# RLS.net
KiCad netlist of a schematic drawn in Altium Designer
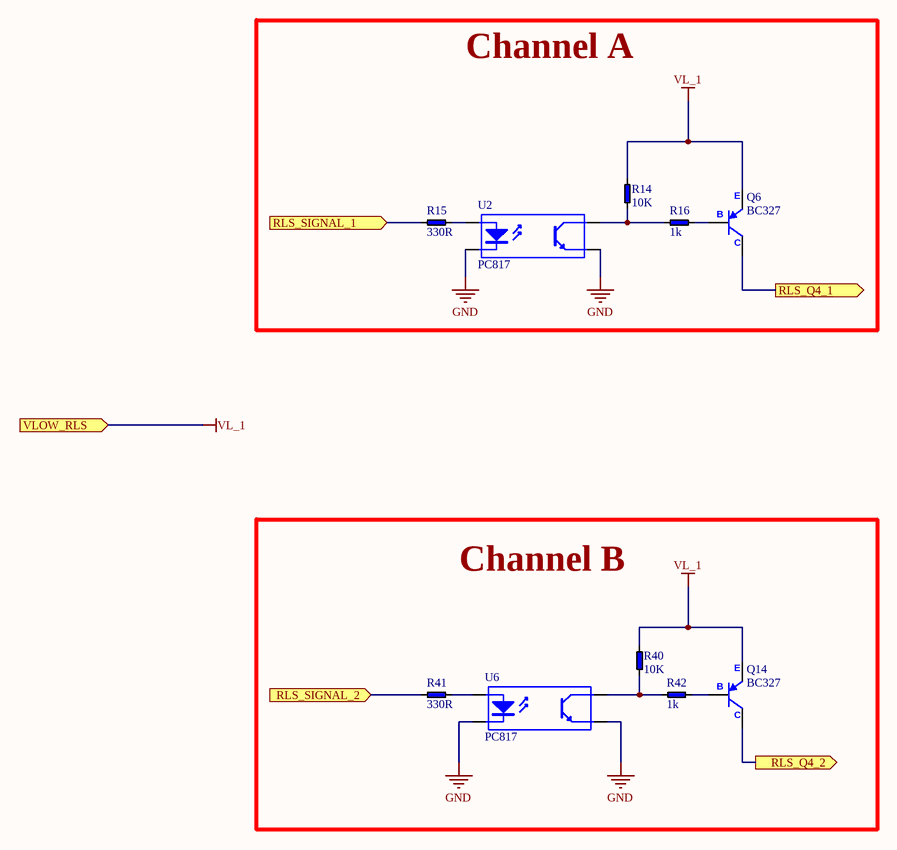
[diagram p0: RLS.SchDoc]

(export (version "E")
  (design (tool "Eeschema 10.0.6"))
  (components
    (comp (ref "Q6")
      (value "BC327")
      (footprint "Transistor - duplicate3")
      (libsource (lib "Altium_Abbas") (part "PNP"))
    )
    (comp (ref "Q14")
      (value "BC327")
      (footprint "Transistor - duplicate3")
      (libsource (lib "Altium_Abbas") (part "PNP"))
    )
    (comp (ref "R14")
      (value "10K")
      (footprint "RESISTOR _9")
      (libsource (lib "Altium_Abbas") (part "RESISTOR"))
    )
    (comp (ref "R15")
      (value "330R")
      (footprint "RESISTOR _9")
      (libsource (lib "Altium_Abbas") (part "RESISTOR"))
    )
    (comp (ref "R16")
      (value "1k")
      (footprint "RESISTOR _9")
      (libsource (lib "Altium_Abbas") (part "RESISTOR"))
    )
    (comp (ref "R40")
      (value "10K")
      (footprint "RESISTOR _9")
      (libsource (lib "Altium_Abbas") (part "RESISTOR"))
    )
    (comp (ref "R41")
      (value "330R")
      (footprint "RESISTOR _9")
      (libsource (lib "Altium_Abbas") (part "RESISTOR"))
    )
    (comp (ref "R42")
      (value "1k")
      (footprint "RESISTOR _9")
      (libsource (lib "Altium_Abbas") (part "RESISTOR"))
    )
    (comp (ref "U2")
      (value "PC817")
      (footprint "IC X4 PIN")
      (description "4-Pin Phototransistor Optocoupler")
      (fields (field (name "PUBLISHER") "Altium Limited"))
      (libsource (lib "Altium_Abbas") (part "Opto-coupler"))
    )
    (comp (ref "U6")
      (value "PC817")
      (footprint "IC X4 PIN")
      (description "4-Pin Phototransistor Optocoupler")
      (fields (field (name "PUBLISHER") "Altium Limited"))
      (libsource (lib "Altium_Abbas") (part "Opto-coupler"))
    )
  )
  (nets
    (net (code "1") (name "/RLS_Q4_1") (class "Default")
      (node (ref "Q6") (pin "3") (pinfunction "C_3") (pintype "passive"))
    )
    (net (code "2") (name "/RLS_Q4_2") (class "Default")
      (node (ref "Q14") (pin "3") (pinfunction "C_3") (pintype "passive"))
    )
    (net (code "3") (name "/RLS_SIGNAL_1") (class "Default")
      (node (ref "R15") (pin "1") (pinfunction "5_1") (pintype "passive"))
    )
    (net (code "4") (name "/RLS_SIGNAL_2") (class "Default")
      (node (ref "R41") (pin "1") (pinfunction "5_1") (pintype "passive"))
    )
    (net (code "5") (name "GND") (class "Default")
      (node (ref "U2") (pin "2") (pinfunction "K_2") (pintype "passive"))
      (node (ref "U2") (pin "3") (pinfunction "E_3") (pintype "passive"))
      (node (ref "U6") (pin "2") (pinfunction "K_2") (pintype "passive"))
      (node (ref "U6") (pin "3") (pinfunction "E_3") (pintype "passive"))
    )
    (net (code "6") (name "Net-(Q6-B)") (class "Default")
      (node (ref "Q6") (pin "2") (pinfunction "B_2") (pintype "passive"))
      (node (ref "R16") (pin "2") (pinfunction "6_2") (pintype "passive"))
    )
    (net (code "7") (name "Net-(Q14-B)") (class "Default")
      (node (ref "Q14") (pin "2") (pinfunction "B_2") (pintype "passive"))
      (node (ref "R42") (pin "2") (pinfunction "6_2") (pintype "passive"))
    )
    (net (code "8") (name "Net-(R14-5)") (class "Default")
      (node (ref "R14") (pin "1") (pinfunction "5_1") (pintype "passive"))
      (node (ref "R16") (pin "1") (pinfunction "5_1") (pintype "passive"))
      (node (ref "U2") (pin "4") (pinfunction "C_4") (pintype "passive"))
    )
    (net (code "9") (name "Net-(R15-6)") (class "Default")
      (node (ref "R15") (pin "2") (pinfunction "6_2") (pintype "passive"))
      (node (ref "U2") (pin "1") (pinfunction "A_1") (pintype "passive"))
    )
    (net (code "10") (name "Net-(R40-5)") (class "Default")
      (node (ref "R40") (pin "1") (pinfunction "5_1") (pintype "passive"))
      (node (ref "R42") (pin "1") (pinfunction "5_1") (pintype "passive"))
      (node (ref "U6") (pin "4") (pinfunction "C_4") (pintype "passive"))
    )
    (net (code "11") (name "Net-(R41-6)") (class "Default")
      (node (ref "R41") (pin "2") (pinfunction "6_2") (pintype "passive"))
      (node (ref "U6") (pin "1") (pinfunction "A_1") (pintype "passive"))
    )
    (net (code "12") (name "VL_1") (class "Default")
      (node (ref "Q14") (pin "1") (pinfunction "E_1") (pintype "passive"))
      (node (ref "Q6") (pin "1") (pinfunction "E_1") (pintype "passive"))
      (node (ref "R14") (pin "2") (pinfunction "6_2") (pintype "passive"))
      (node (ref "R40") (pin "2") (pinfunction "6_2") (pintype "passive"))
    )
  )
)
